# v3_2.net
KiCad netlist of a schematic drawn in EAGLE
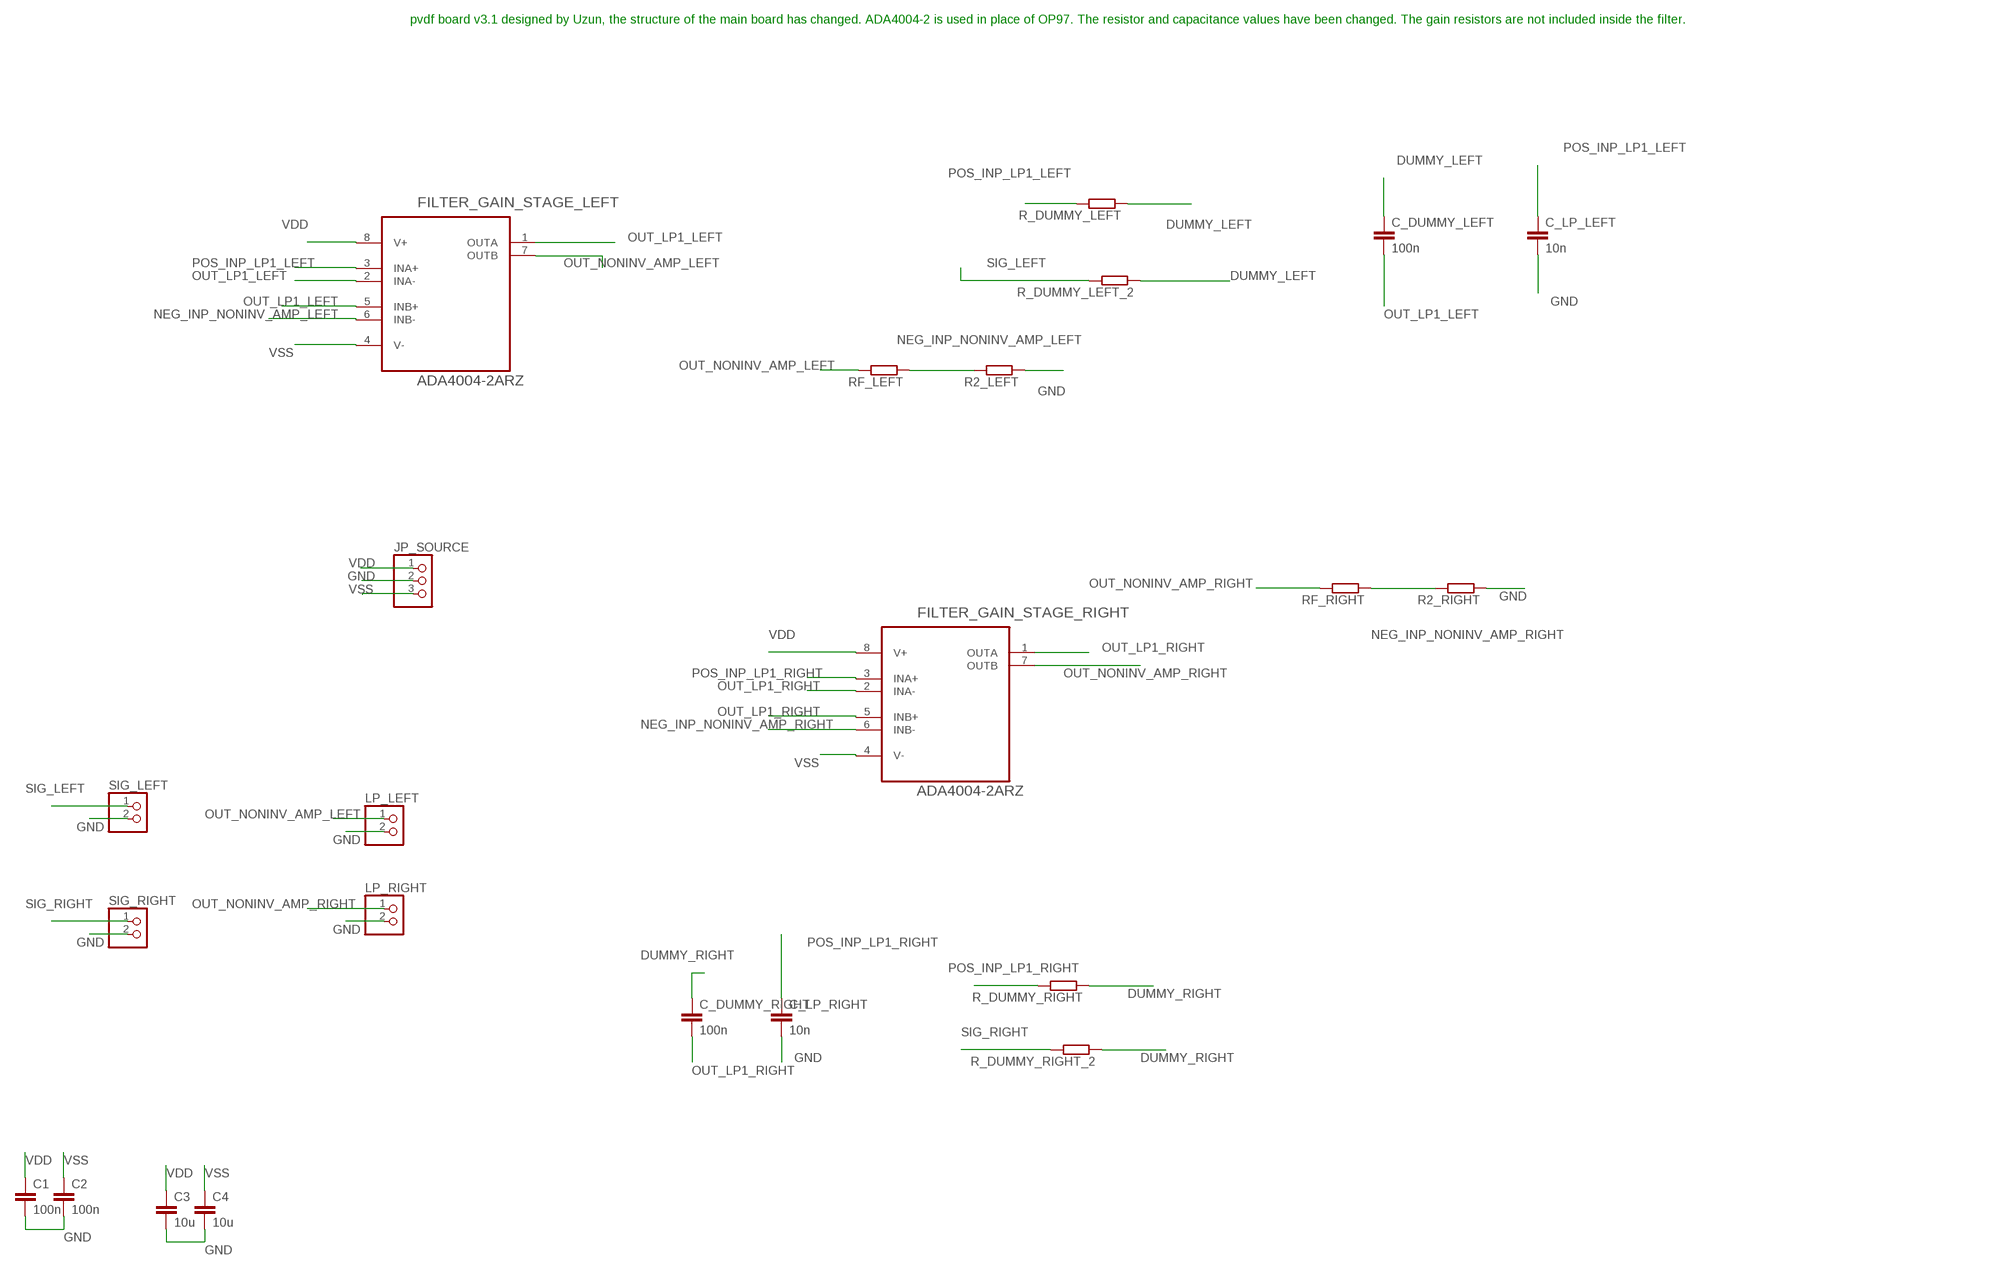
[diagram p0: schematic, sheet 1]

(export (version "E")
  (design (tool "Eeschema 10.0.6"))
  (components
    (comp (ref "C1")
      (value "100n")
      (footprint "eagle-import:C0805")
      (libsource (lib "eagle-import") (part "resistor_348_C-EUC0805"))
    )
    (comp (ref "C2")
      (value "100n")
      (footprint "eagle-import:C0805")
      (libsource (lib "eagle-import") (part "resistor_348_C-EUC0805"))
    )
    (comp (ref "C3")
      (value "10u")
      (footprint "eagle-import:C0805")
      (libsource (lib "eagle-import") (part "resistor_348_C-EUC0805"))
    )
    (comp (ref "C4")
      (value "10u")
      (footprint "eagle-import:C0805")
      (libsource (lib "eagle-import") (part "resistor_348_C-EUC0805"))
    )
    (comp (ref "C_DUMMY_LEFT")
      (value "100n")
      (footprint "eagle-import:C0805")
      (libsource (lib "eagle-import") (part "C-EUC0805"))
    )
    (comp (ref "C_DUMMY_RIGHT")
      (value "100n")
      (footprint "eagle-import:C0805")
      (libsource (lib "eagle-import") (part "C-EUC0805"))
    )
    (comp (ref "C_LP_LEFT")
      (value "10n")
      (footprint "eagle-import:C0805")
      (libsource (lib "eagle-import") (part "C-EUC0805"))
    )
    (comp (ref "C_LP_RIGHT")
      (value "10n")
      (footprint "eagle-import:C0805")
      (libsource (lib "eagle-import") (part "C-EUC0805"))
    )
    (comp (ref "FILTER_GAIN_STAGE_LEFT")
      (value "ADA4004-2ARZ")
      (footprint "eagle-import:SOIC127P600X175-8N")
      (libsource (lib "eagle-import") (part "ADA4004-2ARZ"))
    )
    (comp (ref "FILTER_GAIN_STAGE_RIGHT")
      (value "ADA4004-2ARZ")
      (footprint "eagle-import:SOIC127P600X175-8N")
      (libsource (lib "eagle-import") (part "ADA4004-2ARZ"))
    )
    (comp (ref "JP_SOURCE")
      (value "PINHD-1X3")
      (footprint "eagle-import:1X03")
      (libsource (lib "eagle-import") (part "PINHD-1X3"))
    )
    (comp (ref "LP_LEFT")
      (value "PINHD-1X2")
      (footprint "eagle-import:1X02")
      (libsource (lib "eagle-import") (part "PINHD-1X2"))
    )
    (comp (ref "LP_RIGHT")
      (value "PINHD-1X2")
      (footprint "eagle-import:1X02")
      (libsource (lib "eagle-import") (part "PINHD-1X2"))
    )
    (comp (ref "R2_LEFT")
      (value "6.8k")
      (footprint "eagle-import:M0805")
      (libsource (lib "eagle-import") (part "R-EU_M0805"))
    )
    (comp (ref "R2_RIGHT")
      (value "6.8k")
      (footprint "eagle-import:M0805")
      (libsource (lib "eagle-import") (part "R-EU_M0805"))
    )
    (comp (ref "RF_LEFT")
      (value "330k")
      (footprint "eagle-import:M0805")
      (libsource (lib "eagle-import") (part "R-EU_M0805"))
    )
    (comp (ref "RF_RIGHT")
      (value "330k")
      (footprint "eagle-import:M0805")
      (libsource (lib "eagle-import") (part "R-EU_M0805"))
    )
    (comp (ref "R_DUMMY_LEFT")
      (value "1M")
      (footprint "eagle-import:M0805")
      (libsource (lib "eagle-import") (part "R-EU_M0805"))
    )
    (comp (ref "R_DUMMY_LEFT_2")
      (value "68k")
      (footprint "eagle-import:M0805")
      (libsource (lib "eagle-import") (part "R-EU_M0805"))
    )
    (comp (ref "R_DUMMY_RIGHT")
      (value "1M")
      (footprint "eagle-import:M0805")
      (libsource (lib "eagle-import") (part "R-EU_M0805"))
    )
    (comp (ref "R_DUMMY_RIGHT_2")
      (value "68k")
      (footprint "eagle-import:M0805")
      (libsource (lib "eagle-import") (part "R-EU_M0805"))
    )
    (comp (ref "SIG_LEFT")
      (value "PINHD-1X2")
      (footprint "eagle-import:1X02")
      (libsource (lib "eagle-import") (part "PINHD-1X2"))
    )
    (comp (ref "SIG_RIGHT")
      (value "PINHD-1X2")
      (footprint "eagle-import:1X02")
      (libsource (lib "eagle-import") (part "PINHD-1X2"))
    )
  )
  (nets
    (net (code "1") (name "/DUMMY_LEFT") (class "Default")
      (node (ref "C_DUMMY_LEFT") (pin "1") (pinfunction "1_1") (pintype "passive"))
      (node (ref "R_DUMMY_LEFT") (pin "1") (pinfunction "1_1") (pintype "passive"))
      (node (ref "R_DUMMY_LEFT_2") (pin "1") (pinfunction "1_1") (pintype "passive"))
    )
    (net (code "2") (name "/DUMMY_RIGHT") (class "Default")
      (node (ref "C_DUMMY_RIGHT") (pin "1") (pinfunction "1_1") (pintype "passive"))
      (node (ref "R_DUMMY_RIGHT") (pin "1") (pinfunction "1_1") (pintype "passive"))
      (node (ref "R_DUMMY_RIGHT_2") (pin "1") (pinfunction "1_1") (pintype "passive"))
    )
    (net (code "3") (name "/GND") (class "Default")
      (node (ref "C1") (pin "2") (pinfunction "2_2") (pintype "passive"))
      (node (ref "C2") (pin "2") (pinfunction "2_2") (pintype "passive"))
      (node (ref "C3") (pin "2") (pinfunction "2_2") (pintype "passive"))
      (node (ref "C4") (pin "2") (pinfunction "2_2") (pintype "passive"))
      (node (ref "C_LP_LEFT") (pin "2") (pinfunction "2_2") (pintype "passive"))
      (node (ref "C_LP_RIGHT") (pin "2") (pinfunction "2_2") (pintype "passive"))
      (node (ref "JP_SOURCE") (pin "2") (pinfunction "2_2") (pintype "passive"))
      (node (ref "LP_LEFT") (pin "2") (pinfunction "2_2") (pintype "passive"))
      (node (ref "LP_RIGHT") (pin "2") (pinfunction "2_2") (pintype "passive"))
      (node (ref "R2_LEFT") (pin "1") (pinfunction "1_1") (pintype "passive"))
      (node (ref "R2_RIGHT") (pin "1") (pinfunction "1_1") (pintype "passive"))
      (node (ref "SIG_LEFT") (pin "2") (pinfunction "2_2") (pintype "passive"))
      (node (ref "SIG_RIGHT") (pin "2") (pinfunction "2_2") (pintype "passive"))
    )
    (net (code "4") (name "/NEG_INP_NONINV_AMP_LEFT") (class "Default")
      (node (ref "FILTER_GAIN_STAGE_LEFT") (pin "6") (pinfunction "INB-_6") (pintype "input"))
      (node (ref "R2_LEFT") (pin "2") (pinfunction "2_2") (pintype "passive"))
      (node (ref "RF_LEFT") (pin "1") (pinfunction "1_1") (pintype "passive"))
    )
    (net (code "5") (name "/NEG_INP_NONINV_AMP_RIGHT") (class "Default")
      (node (ref "FILTER_GAIN_STAGE_RIGHT") (pin "6") (pinfunction "INB-_6") (pintype "input"))
      (node (ref "R2_RIGHT") (pin "2") (pinfunction "2_2") (pintype "passive"))
      (node (ref "RF_RIGHT") (pin "1") (pinfunction "1_1") (pintype "passive"))
    )
    (net (code "6") (name "/OUT_LP1_LEFT") (class "Default")
      (node (ref "C_DUMMY_LEFT") (pin "2") (pinfunction "2_2") (pintype "passive"))
      (node (ref "FILTER_GAIN_STAGE_LEFT") (pin "1") (pinfunction "OUTA_1") (pintype "output"))
      (node (ref "FILTER_GAIN_STAGE_LEFT") (pin "2") (pinfunction "INA-_2") (pintype "input"))
      (node (ref "FILTER_GAIN_STAGE_LEFT") (pin "5") (pinfunction "INB+_5") (pintype "input"))
    )
    (net (code "7") (name "/OUT_LP1_RIGHT") (class "Default")
      (node (ref "C_DUMMY_RIGHT") (pin "2") (pinfunction "2_2") (pintype "passive"))
      (node (ref "FILTER_GAIN_STAGE_RIGHT") (pin "1") (pinfunction "OUTA_1") (pintype "output"))
      (node (ref "FILTER_GAIN_STAGE_RIGHT") (pin "2") (pinfunction "INA-_2") (pintype "input"))
      (node (ref "FILTER_GAIN_STAGE_RIGHT") (pin "5") (pinfunction "INB+_5") (pintype "input"))
    )
    (net (code "8") (name "/OUT_NONINV_AMP_LEFT") (class "Default")
      (node (ref "FILTER_GAIN_STAGE_LEFT") (pin "7") (pinfunction "OUTB_7") (pintype "output"))
      (node (ref "LP_LEFT") (pin "1") (pinfunction "1_1") (pintype "passive"))
      (node (ref "RF_LEFT") (pin "2") (pinfunction "2_2") (pintype "passive"))
    )
    (net (code "9") (name "/OUT_NONINV_AMP_RIGHT") (class "Default")
      (node (ref "FILTER_GAIN_STAGE_RIGHT") (pin "7") (pinfunction "OUTB_7") (pintype "output"))
      (node (ref "LP_RIGHT") (pin "1") (pinfunction "1_1") (pintype "passive"))
      (node (ref "RF_RIGHT") (pin "2") (pinfunction "2_2") (pintype "passive"))
    )
    (net (code "10") (name "/POS_INP_LP1_LEFT") (class "Default")
      (node (ref "C_LP_LEFT") (pin "1") (pinfunction "1_1") (pintype "passive"))
      (node (ref "FILTER_GAIN_STAGE_LEFT") (pin "3") (pinfunction "INA+_3") (pintype "input"))
      (node (ref "R_DUMMY_LEFT") (pin "2") (pinfunction "2_2") (pintype "passive"))
    )
    (net (code "11") (name "/POS_INP_LP1_RIGHT") (class "Default")
      (node (ref "C_LP_RIGHT") (pin "1") (pinfunction "1_1") (pintype "passive"))
      (node (ref "FILTER_GAIN_STAGE_RIGHT") (pin "3") (pinfunction "INA+_3") (pintype "input"))
      (node (ref "R_DUMMY_RIGHT") (pin "2") (pinfunction "2_2") (pintype "passive"))
    )
    (net (code "12") (name "/SIG_LEFT") (class "Default")
      (node (ref "R_DUMMY_LEFT_2") (pin "2") (pinfunction "2_2") (pintype "passive"))
      (node (ref "SIG_LEFT") (pin "1") (pinfunction "1_1") (pintype "passive"))
    )
    (net (code "13") (name "/SIG_RIGHT") (class "Default")
      (node (ref "R_DUMMY_RIGHT_2") (pin "2") (pinfunction "2_2") (pintype "passive"))
      (node (ref "SIG_RIGHT") (pin "1") (pinfunction "1_1") (pintype "passive"))
    )
    (net (code "14") (name "/VDD") (class "Default")
      (node (ref "C1") (pin "1") (pinfunction "1_1") (pintype "passive"))
      (node (ref "C3") (pin "1") (pinfunction "1_1") (pintype "passive"))
      (node (ref "FILTER_GAIN_STAGE_LEFT") (pin "8") (pinfunction "V+_8") (pintype "power_in"))
      (node (ref "FILTER_GAIN_STAGE_RIGHT") (pin "8") (pinfunction "V+_8") (pintype "power_in"))
      (node (ref "JP_SOURCE") (pin "1") (pinfunction "1_1") (pintype "passive"))
    )
    (net (code "15") (name "/VSS") (class "Default")
      (node (ref "C2") (pin "1") (pinfunction "1_1") (pintype "passive"))
      (node (ref "C4") (pin "1") (pinfunction "1_1") (pintype "passive"))
      (node (ref "FILTER_GAIN_STAGE_LEFT") (pin "4") (pinfunction "V-_4") (pintype "power_in"))
      (node (ref "FILTER_GAIN_STAGE_RIGHT") (pin "4") (pinfunction "V-_4") (pintype "power_in"))
      (node (ref "JP_SOURCE") (pin "3") (pinfunction "3_3") (pintype "passive"))
    )
  )
)
